# sd_card.net
KiCad netlist of a schematic drawn in Altium Designer
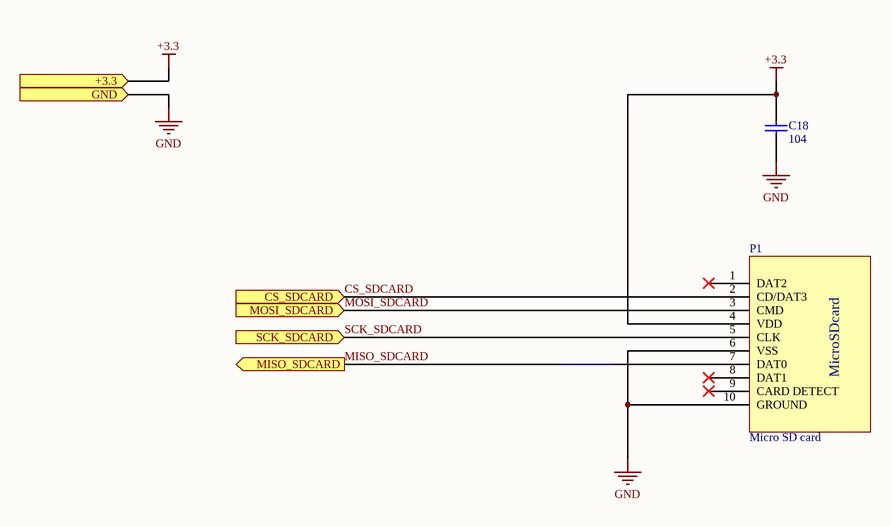
[diagram p0: sd_card.SchDoc]

(export (version "E")
  (design (tool "Eeschema 10.0.6"))
  (components
    (comp (ref "C18")
      (value "104")
      (footprint "tu 0603")
      (description "Dán")
      (libsource (lib "TrungVan_Lib") (part "Tu 0603 104 50V 10%"))
    )
    (comp (ref "P1")
      (value "Micro SD card")
      (footprint "MicroSD")
      (libsource (lib "TrungVan_Lib") (part "Micro SD card"))
    )
  )
  (nets
    (net (code "1") (name "+3.3") (class "Default")
      (node (ref "C18") (pin "1") (pinfunction "1_1") (pintype "passive"))
      (node (ref "P1") (pin "4") (pinfunction "VDD_4") (pintype "passive"))
    )
    (net (code "2") (name "/CS_SDCARD") (class "Default")
      (node (ref "P1") (pin "2") (pinfunction "CD/DAT3_2") (pintype "passive"))
    )
    (net (code "3") (name "/MISO_SDCARD") (class "Default")
      (node (ref "P1") (pin "7") (pinfunction "DAT0_7") (pintype "passive"))
    )
    (net (code "4") (name "/MOSI_SDCARD") (class "Default")
      (node (ref "P1") (pin "3") (pinfunction "CMD_3") (pintype "passive"))
    )
    (net (code "5") (name "/SCK_SDCARD") (class "Default")
      (node (ref "P1") (pin "5") (pinfunction "CLK_5") (pintype "passive"))
    )
    (net (code "6") (name "GND") (class "Default")
      (node (ref "C18") (pin "2") (pinfunction "2_2") (pintype "passive"))
      (node (ref "P1") (pin "10") (pinfunction "GROUND_10") (pintype "passive"))
      (node (ref "P1") (pin "6") (pinfunction "VSS_6") (pintype "passive"))
    )
    (net (code "7") (name "unconnected-(P1-CARD_DETECT-Pad9)") (class "Default")
      (node (ref "P1") (pin "9") (pinfunction "CARD_DETECT_9") (pintype "passive+no_connect"))
    )
    (net (code "8") (name "unconnected-(P1-DAT1-Pad8)") (class "Default")
      (node (ref "P1") (pin "8") (pinfunction "DAT1_8") (pintype "passive+no_connect"))
    )
    (net (code "9") (name "unconnected-(P1-DAT2-Pad1)") (class "Default")
      (node (ref "P1") (pin "1") (pinfunction "DAT2_1") (pintype "passive+no_connect"))
    )
  )
)
